# MCU103A_Connectors.net
KiCad netlist of a schematic drawn in Altium Designer
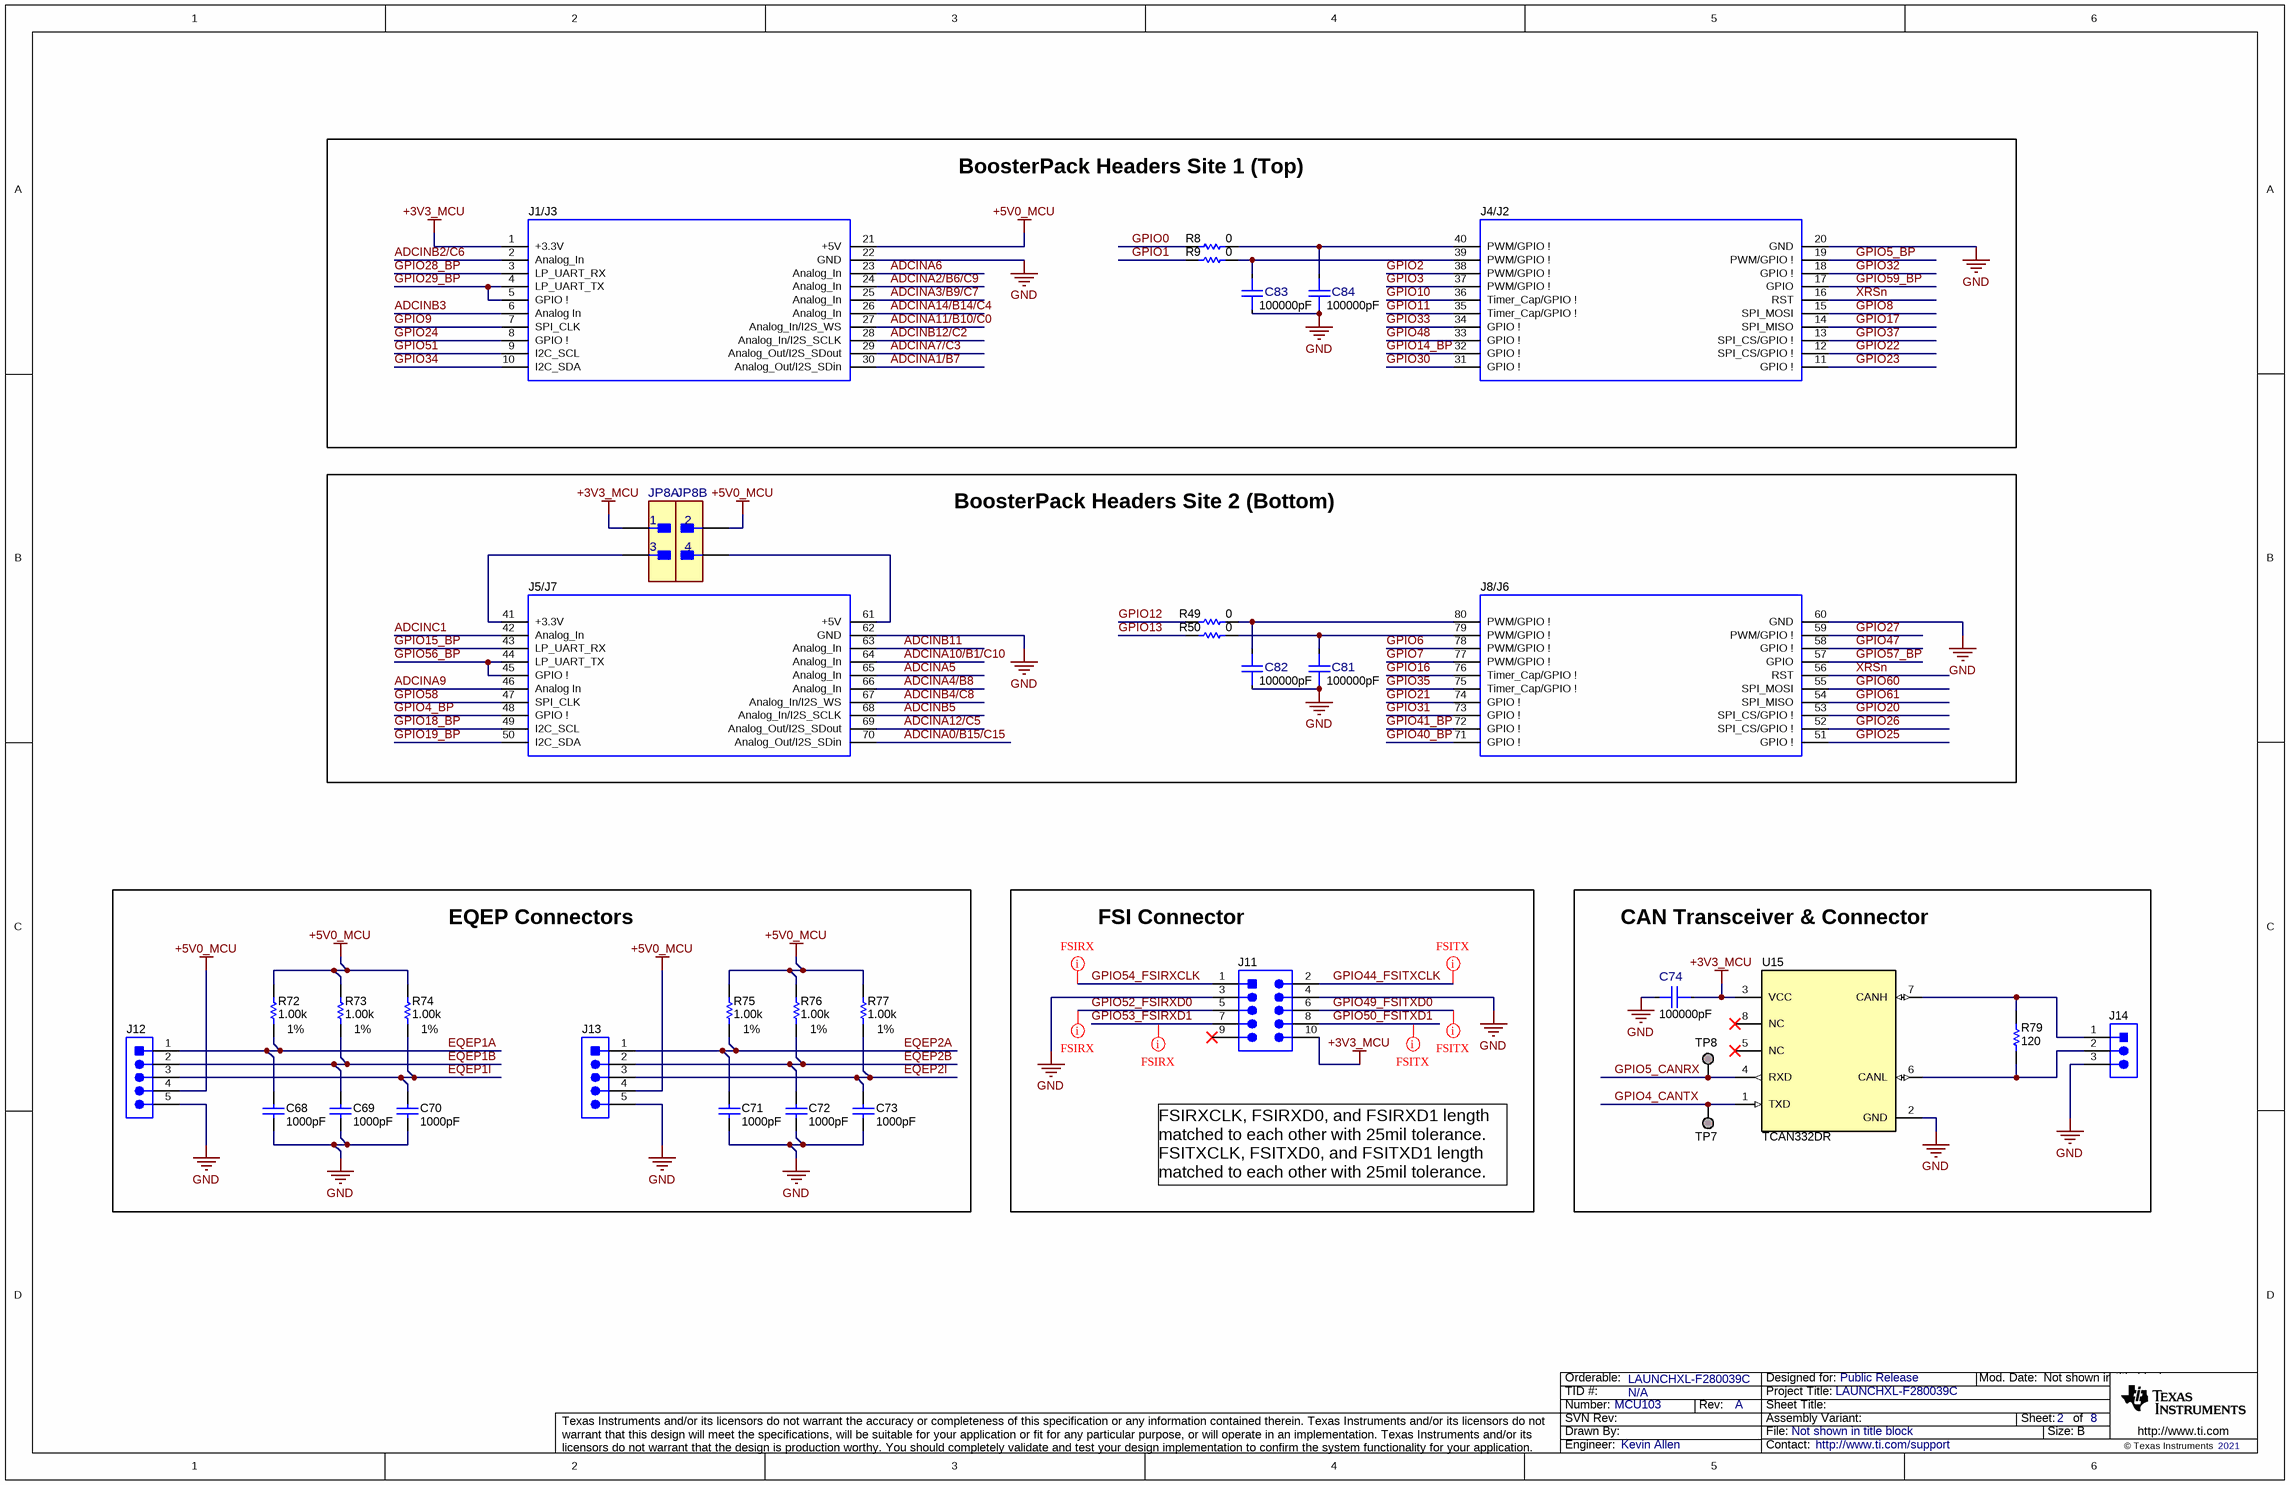
[diagram p0: MCU103A_Connectors.SchDoc]

(export (version "E")
  (design (tool "Eeschema 10.0.6"))
  (components
    (comp (ref "C68")
      (value "885012205061")
      (footprint "0402")
      (description "CAP, CERM, 1000 pF, 50 V, +/- 10%, X7R, 0402")
      (fields
        (field (name "VALUEDISPLAYED") "1000pF")
        (field (name "MANUFACTURER") "Wurth Elektronik")
        (field (name "PUBLISHER") "Texas Instruments")
      )
      (libsource (lib "Altium Vault - TI") (part "Capacitor"))
    )
    (comp (ref "C69")
      (value "885012205061")
      (footprint "0402")
      (description "CAP, CERM, 1000 pF, 50 V, +/- 10%, X7R, 0402")
      (fields
        (field (name "VALUEDISPLAYED") "1000pF")
        (field (name "MANUFACTURER") "Wurth Elektronik")
        (field (name "PUBLISHER") "Texas Instruments")
      )
      (libsource (lib "Altium Vault - TI") (part "Capacitor"))
    )
    (comp (ref "C70")
      (value "885012205061")
      (footprint "0402")
      (description "CAP, CERM, 1000 pF, 50 V, +/- 10%, X7R, 0402")
      (fields
        (field (name "VALUEDISPLAYED") "1000pF")
        (field (name "MANUFACTURER") "Wurth Elektronik")
        (field (name "PUBLISHER") "Texas Instruments")
      )
      (libsource (lib "Altium Vault - TI") (part "Capacitor"))
    )
    (comp (ref "C71")
      (value "885012205061")
      (footprint "0402")
      (description "CAP, CERM, 1000 pF, 50 V, +/- 10%, X7R, 0402")
      (fields
        (field (name "VALUEDISPLAYED") "1000pF")
        (field (name "MANUFACTURER") "Wurth Elektronik")
        (field (name "PUBLISHER") "Texas Instruments")
      )
      (libsource (lib "Altium Vault - TI") (part "Capacitor"))
    )
    (comp (ref "C72")
      (value "885012205061")
      (footprint "0402")
      (description "CAP, CERM, 1000 pF, 50 V, +/- 10%, X7R, 0402")
      (fields
        (field (name "VALUEDISPLAYED") "1000pF")
        (field (name "MANUFACTURER") "Wurth Elektronik")
        (field (name "PUBLISHER") "Texas Instruments")
      )
      (libsource (lib "Altium Vault - TI") (part "Capacitor"))
    )
    (comp (ref "C73")
      (value "885012205061")
      (footprint "0402")
      (description "CAP, CERM, 1000 pF, 50 V, +/- 10%, X7R, 0402")
      (fields
        (field (name "VALUEDISPLAYED") "1000pF")
        (field (name "MANUFACTURER") "Wurth Elektronik")
        (field (name "PUBLISHER") "Texas Instruments")
      )
      (libsource (lib "Altium Vault - TI") (part "Capacitor"))
    )
    (comp (ref "C74")
      (value "885012205018")
      (footprint "FP-885012205018_0402-MFG")
      (description "0.1µF ±10% 10V Ceramic Capacitor X7R 0402 (1005 Metric)")
      (fields
        (field (name "MANUFACTURER") "Wurth Electronics")
        (field (name "MOUSER PART NUMBER") "710-885012205018")
        (field (name "VALUEDISPLAYED") "100000pF")
      )
      (libsource (lib "Altium Vault - TI") (part "SYM-885012205018"))
    )
    (comp (ref "C81")
      (value "885012205018")
      (footprint "FP-885012205018_0402-MFG")
      (description "0.1µF ±10% 10V Ceramic Capacitor X7R 0402 (1005 Metric)")
      (fields
        (field (name "MANUFACTURER") "Wurth Electronics")
        (field (name "MOUSER PART NUMBER") "710-885012205018")
        (field (name "VALUEDISPLAYED") "100000pF")
      )
      (libsource (lib "Altium Vault - TI") (part "SYM-885012205018"))
    )
    (comp (ref "C82")
      (value "885012205018")
      (footprint "FP-885012205018_0402-MFG")
      (description "0.1µF ±10% 10V Ceramic Capacitor X7R 0402 (1005 Metric)")
      (fields
        (field (name "MANUFACTURER") "Wurth Electronics")
        (field (name "MOUSER PART NUMBER") "710-885012205018")
        (field (name "VALUEDISPLAYED") "100000pF")
      )
      (libsource (lib "Altium Vault - TI") (part "SYM-885012205018"))
    )
    (comp (ref "C83")
      (value "885012205018")
      (footprint "FP-885012205018_0402-MFG")
      (description "0.1µF ±10% 10V Ceramic Capacitor X7R 0402 (1005 Metric)")
      (fields
        (field (name "MANUFACTURER") "Wurth Electronics")
        (field (name "MOUSER PART NUMBER") "710-885012205018")
        (field (name "VALUEDISPLAYED") "100000pF")
      )
      (libsource (lib "Altium Vault - TI") (part "SYM-885012205018"))
    )
    (comp (ref "C84")
      (value "885012205018")
      (footprint "FP-885012205018_0402-MFG")
      (description "0.1µF ±10% 10V Ceramic Capacitor X7R 0402 (1005 Metric)")
      (fields
        (field (name "MANUFACTURER") "Wurth Electronics")
        (field (name "MOUSER PART NUMBER") "710-885012205018")
        (field (name "VALUEDISPLAYED") "100000pF")
      )
      (libsource (lib "Altium Vault - TI") (part "SYM-885012205018"))
    )
    (comp (ref "J1/J3")
      (value "SSQ-110-03-T-D")
      (footprint "BoosterPack_40pin_J1J3")
      (description "Receptacle, 2.54mm, 10x2, Tin, TH")
      (fields (field (name "ALTERNATE PARTNUMBER") "CRD-081413-A-G") (field (name "MANUFACTURER") "Samtec"))
      (libsource (lib "Altium Vault - TI") (part "BoosterPack_40pin_J1J3"))
    )
    (comp (ref "J4/J2")
      (value "SSQ-110-03-T-D")
      (footprint "BoosterPack_40pin_J2J4")
      (description "Receptacle, 2.54mm, 10x2, Tin, TH")
      (fields (field (name "ALTERNATE PARTNUMBER") "CRD-081413-A-G") (field (name "MANUFACTURER") "Samtec"))
      (libsource (lib "Altium Vault - TI") (part "BoosterPack_40pin_J2J4"))
    )
    (comp (ref "J5/J7")
      (value "SSQ-110-03-T-D")
      (footprint "BoosterPack_40pin_J5J7")
      (description "Receptacle, 2.54mm, 10x2, Tin, TH")
      (fields (field (name "ALTERNATE PARTNUMBER") "CRD-081413-A-G") (field (name "MANUFACTURER") "Samtec"))
      (libsource (lib "Altium Vault - TI") (part "BoosterPack_40pin_J5J7"))
    )
    (comp (ref "J8/J6")
      (value "SSQ-110-03-T-D")
      (footprint "BoosterPack_40pin_J6J8")
      (description "Receptacle, 2.54mm, 10x2, Tin, TH")
      (fields (field (name "ALTERNATE PARTNUMBER") "CRD-081413-A-G") (field (name "MANUFACTURER") "Samtec"))
      (libsource (lib "Altium Vault - TI") (part "BoosterPack_40pin_J6J8"))
    )
    (comp (ref "J11")
      (value "61301021121")
      (footprint "WURTH_61301021121")
      (description "Header, 2.54 mm, 5x2, Gold, TH")
      (fields (field (name "MANUFACTURER") "Wurth Elektronik"))
      (libsource (lib "Altium Vault - TI") (part "Header_5x2"))
    )
    (comp (ref "J12")
      (value "61300511121")
      (footprint "Wurth_61300511121")
      (description "Header, 2.54mm, 5x1, Gold, TH")
      (fields (field (name "MANUFACTURER") "Wurth Elektronik"))
      (libsource (lib "Altium Vault - TI") (part "Header_5x1"))
    )
    (comp (ref "J13")
      (value "61300511121")
      (footprint "Wurth_61300511121")
      (description "Header, 2.54mm, 5x1, Gold, TH")
      (fields (field (name "MANUFACTURER") "Wurth Elektronik"))
      (libsource (lib "Altium Vault - TI") (part "Header_5x1"))
    )
    (comp (ref "J14")
      (value "61300311121")
      (footprint "WURTH_61300311121")
      (description "Header, 2.54 mm, 3x1, Gold, TH")
      (fields (field (name "MANUFACTURER") "Wurth Elektronik") (field (name "PUBLISHER") "Texas Instruments"))
      (libsource (lib "Altium Vault - TI") (part "Header_3x1"))
    )
    (comp (ref "JP8")
      (value "61300421121")
      (footprint "FP-61300421121_HDR4-MFG")
      (description "THT Vertical Pin Header WR-PHD, Pitch 2.54 mm, Dual Row, 4 pins")
      (fields
        (field (name "MANUFACTURER") "Wurth Electronics")
        (field (name "MOUSER PART NUMBER") "710-61300421121")
      )
      (libsource (lib "") (part "SYM-61300421121_1"))
    )
    (comp (ref "R8")
      (value "RC0402JR-070RL")
      (footprint "0402")
      (description "RES, 0, 5%, 0.063 W, 0402")
      (fields
        (field (name "MANUFACTURER") "Yageo America")
        (field (name "VALUEDISPLAYED") "0")
        (field (name "PUBLISHER") "Texas Instruments")
      )
      (libsource (lib "Altium Vault - TI") (part "Resistor"))
    )
    (comp (ref "R9")
      (value "RC0402JR-070RL")
      (footprint "0402")
      (description "RES, 0, 5%, 0.063 W, 0402")
      (fields
        (field (name "MANUFACTURER") "Yageo America")
        (field (name "VALUEDISPLAYED") "0")
        (field (name "PUBLISHER") "Texas Instruments")
      )
      (libsource (lib "Altium Vault - TI") (part "Resistor"))
    )
    (comp (ref "R49")
      (value "RC0402JR-070RL")
      (footprint "0402")
      (description "RES, 0, 5%, 0.063 W, 0402")
      (fields
        (field (name "MANUFACTURER") "Yageo America")
        (field (name "VALUEDISPLAYED") "0")
        (field (name "PUBLISHER") "Texas Instruments")
      )
      (libsource (lib "Altium Vault - TI") (part "Resistor"))
    )
    (comp (ref "R50")
      (value "RC0402JR-070RL")
      (footprint "0402")
      (description "RES, 0, 5%, 0.063 W, 0402")
      (fields
        (field (name "MANUFACTURER") "Yageo America")
        (field (name "VALUEDISPLAYED") "0")
        (field (name "PUBLISHER") "Texas Instruments")
      )
      (libsource (lib "Altium Vault - TI") (part "Resistor"))
    )
    (comp (ref "R72")
      (value "CRCW04021K00FKED")
      (footprint "0402")
      (description "RES, 1.00 k, 1%, 0.063 W, AEC-Q200 Grade 0, 0402")
      (fields
        (field (name "VALUEDISPLAYED") "1.00k")
        (field (name "MANUFACTURER") "Vishay-Dale")
        (field (name "VALUE1") "1%")
      )
      (libsource (lib "Altium Vault - TI") (part "Resistor"))
    )
    (comp (ref "R73")
      (value "CRCW04021K00FKED")
      (footprint "0402")
      (description "RES, 1.00 k, 1%, 0.063 W, AEC-Q200 Grade 0, 0402")
      (fields
        (field (name "VALUEDISPLAYED") "1.00k")
        (field (name "MANUFACTURER") "Vishay-Dale")
        (field (name "VALUE1") "1%")
      )
      (libsource (lib "Altium Vault - TI") (part "Resistor"))
    )
    (comp (ref "R74")
      (value "CRCW04021K00FKED")
      (footprint "0402")
      (description "RES, 1.00 k, 1%, 0.063 W, AEC-Q200 Grade 0, 0402")
      (fields
        (field (name "VALUEDISPLAYED") "1.00k")
        (field (name "MANUFACTURER") "Vishay-Dale")
        (field (name "VALUE1") "1%")
      )
      (libsource (lib "Altium Vault - TI") (part "Resistor"))
    )
    (comp (ref "R75")
      (value "CRCW04021K00FKED")
      (footprint "0402")
      (description "RES, 1.00 k, 1%, 0.063 W, AEC-Q200 Grade 0, 0402")
      (fields
        (field (name "VALUEDISPLAYED") "1.00k")
        (field (name "MANUFACTURER") "Vishay-Dale")
        (field (name "VALUE1") "1%")
      )
      (libsource (lib "Altium Vault - TI") (part "Resistor"))
    )
    (comp (ref "R76")
      (value "CRCW04021K00FKED")
      (footprint "0402")
      (description "RES, 1.00 k, 1%, 0.063 W, AEC-Q200 Grade 0, 0402")
      (fields
        (field (name "VALUEDISPLAYED") "1.00k")
        (field (name "MANUFACTURER") "Vishay-Dale")
        (field (name "VALUE1") "1%")
      )
      (libsource (lib "Altium Vault - TI") (part "Resistor"))
    )
    (comp (ref "R77")
      (value "CRCW04021K00FKED")
      (footprint "0402")
      (description "RES, 1.00 k, 1%, 0.063 W, AEC-Q200 Grade 0, 0402")
      (fields
        (field (name "VALUEDISPLAYED") "1.00k")
        (field (name "MANUFACTURER") "Vishay-Dale")
        (field (name "VALUE1") "1%")
      )
      (libsource (lib "Altium Vault - TI") (part "Resistor"))
    )
    (comp (ref "R79")
      (value "RC0603FR-07120RL")
      (footprint "0603")
      (description "RES, 120, 1%, 0.1 W, 0603")
      (fields
        (field (name "VALUEDISPLAYED") "120")
        (field (name "MANUFACTURER") "Yageo America")
        (field (name "PUBLISHER") "Texas Instruments")
      )
      (libsource (lib "Altium Vault - TI") (part "Resistor"))
    )
    (comp (ref "TP7")
      (value "TESTPOINT")
      (footprint "TP_50MIL-25MILHOLE")
      (description "TEST POINT.  No entry in BOM.")
      (libsource (lib "Altium Vault - TI") (part "TESTPOINT"))
    )
    (comp (ref "TP8")
      (value "TESTPOINT")
      (footprint "TP_50MIL-25MILHOLE")
      (description "TEST POINT.  No entry in BOM.")
      (libsource (lib "Altium Vault - TI") (part "TESTPOINT"))
    )
    (comp (ref "U15")
      (value "TCAN332DR")
      (footprint "D0008A_N")
      (description "3.3-V CAN Transceivers, D0008A (SOIC-8)")
      (fields
        (field (name "ALTERNATE PARTNUMBER") "TCAN332D")
        (field (name "MANUFACTURER") "Texas Instruments")
        (field (name "PARTNUMBER") "TCAN332DR")
      )
      (libsource (lib "Altium Vault - TI") (part "TCAN332"))
    )
  )
  (nets
    (net (code "1") (name "+3V3_MCU") (class "Default")
      (node (ref "C74") (pin "1") (pinfunction "1_1") (pintype "passive"))
      (node (ref "J1/J3") (pin "1") (pinfunction "+3.3V_1") (pintype "power_in"))
      (node (ref "J11") (pin "10") (pinfunction "10_10") (pintype "passive"))
      (node (ref "JP8") (pin "1") (pinfunction "1_1") (pintype "passive"))
      (node (ref "U15") (pin "3") (pinfunction "VCC_3") (pintype "power_in"))
    )
    (net (code "2") (name "+5V0_MCU") (class "Default")
      (node (ref "J1/J3") (pin "21") (pinfunction "+5V_21") (pintype "power_in"))
      (node (ref "J12") (pin "4") (pinfunction "4_4") (pintype "passive"))
      (node (ref "J13") (pin "4") (pinfunction "4_4") (pintype "passive"))
      (node (ref "JP8") (pin "2") (pinfunction "2_2") (pintype "passive"))
      (node (ref "R72") (pin "2") (pinfunction "2_2") (pintype "passive"))
      (node (ref "R73") (pin "2") (pinfunction "2_2") (pintype "passive"))
      (node (ref "R74") (pin "2") (pinfunction "2_2") (pintype "passive"))
      (node (ref "R75") (pin "2") (pinfunction "2_2") (pintype "passive"))
      (node (ref "R76") (pin "2") (pinfunction "2_2") (pintype "passive"))
      (node (ref "R77") (pin "2") (pinfunction "2_2") (pintype "passive"))
    )
    (net (code "3") (name "/ADCINA0{slash}B15{slash}C15") (class "Default")
      (node (ref "J5/J7") (pin "70") (pinfunction "Analog_Out/I2S_SDin_70") (pintype "passive"))
    )
    (net (code "4") (name "/ADCINA1{slash}B7") (class "Default")
      (node (ref "J1/J3") (pin "30") (pinfunction "Analog_Out/I2S_SDin_30") (pintype "passive"))
    )
    (net (code "5") (name "/ADCINA2{slash}B6{slash}C9") (class "Default")
      (node (ref "J1/J3") (pin "24") (pinfunction "Analog_In_24") (pintype "passive"))
    )
    (net (code "6") (name "/ADCINA3{slash}B9{slash}C7") (class "Default")
      (node (ref "J1/J3") (pin "25") (pinfunction "Analog_In_25") (pintype "passive"))
    )
    (net (code "7") (name "/ADCINA4{slash}B8") (class "Default")
      (node (ref "J5/J7") (pin "66") (pinfunction "Analog_In_66") (pintype "passive"))
    )
    (net (code "8") (name "/ADCINA5") (class "Default")
      (node (ref "J5/J7") (pin "65") (pinfunction "Analog_In_65") (pintype "passive"))
    )
    (net (code "9") (name "/ADCINA6") (class "Default")
      (node (ref "J1/J3") (pin "23") (pinfunction "Analog_In_23") (pintype "passive"))
    )
    (net (code "10") (name "/ADCINA7{slash}C3") (class "Default")
      (node (ref "J1/J3") (pin "29") (pinfunction "Analog_Out/I2S_SDout_29") (pintype "passive"))
    )
    (net (code "11") (name "/ADCINA9") (class "Default")
      (node (ref "J5/J7") (pin "46") (pinfunction "Analog_In_46") (pintype "passive"))
    )
    (net (code "12") (name "/ADCINA10{slash}B1{slash}C10") (class "Default")
      (node (ref "J5/J7") (pin "64") (pinfunction "Analog_In_64") (pintype "passive"))
    )
    (net (code "13") (name "/ADCINA11{slash}B10{slash}C0") (class "Default")
      (node (ref "J1/J3") (pin "27") (pinfunction "Analog_In/I2S_WS_27") (pintype "passive"))
    )
    (net (code "14") (name "/ADCINA12{slash}C5") (class "Default")
      (node (ref "J5/J7") (pin "69") (pinfunction "Analog_Out/I2S_SDout_69") (pintype "passive"))
    )
    (net (code "15") (name "/ADCINA14{slash}B14{slash}C4") (class "Default")
      (node (ref "J1/J3") (pin "26") (pinfunction "Analog_In_26") (pintype "passive"))
    )
    (net (code "16") (name "/ADCINB2{slash}C6") (class "Default")
      (node (ref "J1/J3") (pin "2") (pinfunction "Analog_In_2") (pintype "passive"))
    )
    (net (code "17") (name "/ADCINB3") (class "Default")
      (node (ref "J1/J3") (pin "6") (pinfunction "Analog_In_6") (pintype "passive"))
    )
    (net (code "18") (name "/ADCINB4{slash}C8") (class "Default")
      (node (ref "J5/J7") (pin "67") (pinfunction "Analog_In/I2S_WS_67") (pintype "passive"))
    )
    (net (code "19") (name "/ADCINB5") (class "Default")
      (node (ref "J5/J7") (pin "68") (pinfunction "Analog_In/I2S_SCLK_68") (pintype "passive"))
    )
    (net (code "20") (name "/ADCINB11") (class "Default")
      (node (ref "J5/J7") (pin "63") (pinfunction "Analog_In_63") (pintype "passive"))
    )
    (net (code "21") (name "/ADCINB12{slash}C2") (class "Default")
      (node (ref "J1/J3") (pin "28") (pinfunction "Analog_In/I2S_SCLK_28") (pintype "passive"))
    )
    (net (code "22") (name "/ADCINC1") (class "Default")
      (node (ref "J5/J7") (pin "42") (pinfunction "Analog_In_42") (pintype "passive"))
    )
    (net (code "23") (name "/EQEP1A") (class "Default")
      (node (ref "C68") (pin "1") (pinfunction "1_1") (pintype "passive"))
      (node (ref "J12") (pin "1") (pinfunction "1_1") (pintype "passive"))
      (node (ref "R72") (pin "1") (pinfunction "1_1") (pintype "passive"))
    )
    (net (code "24") (name "/EQEP1B") (class "Default")
      (node (ref "C69") (pin "1") (pinfunction "1_1") (pintype "passive"))
      (node (ref "J12") (pin "2") (pinfunction "2_2") (pintype "passive"))
      (node (ref "R73") (pin "1") (pinfunction "1_1") (pintype "passive"))
    )
    (net (code "25") (name "/EQEP1I") (class "Default")
      (node (ref "C70") (pin "1") (pinfunction "1_1") (pintype "passive"))
      (node (ref "J12") (pin "3") (pinfunction "3_3") (pintype "passive"))
      (node (ref "R74") (pin "1") (pinfunction "1_1") (pintype "passive"))
    )
    (net (code "26") (name "/EQEP2A") (class "Default")
      (node (ref "C71") (pin "1") (pinfunction "1_1") (pintype "passive"))
      (node (ref "J13") (pin "1") (pinfunction "1_1") (pintype "passive"))
      (node (ref "R75") (pin "1") (pinfunction "1_1") (pintype "passive"))
    )
    (net (code "27") (name "/EQEP2B") (class "Default")
      (node (ref "C72") (pin "1") (pinfunction "1_1") (pintype "passive"))
      (node (ref "J13") (pin "2") (pinfunction "2_2") (pintype "passive"))
      (node (ref "R76") (pin "1") (pinfunction "1_1") (pintype "passive"))
    )
    (net (code "28") (name "/EQEP2I") (class "Default")
      (node (ref "C73") (pin "1") (pinfunction "1_1") (pintype "passive"))
      (node (ref "J13") (pin "3") (pinfunction "3_3") (pintype "passive"))
      (node (ref "R77") (pin "1") (pinfunction "1_1") (pintype "passive"))
    )
    (net (code "29") (name "/GPIO0") (class "Default")
      (node (ref "R8") (pin "1") (pinfunction "1_1") (pintype "passive"))
    )
    (net (code "30") (name "/GPIO1") (class "Default")
      (node (ref "R9") (pin "1") (pinfunction "1_1") (pintype "passive"))
    )
    (net (code "31") (name "/GPIO2") (class "Default")
      (node (ref "J4/J2") (pin "38") (pinfunction "PWM/GPIO_!_38") (pintype "passive"))
    )
    (net (code "32") (name "/GPIO3") (class "Default")
      (node (ref "J4/J2") (pin "37") (pinfunction "PWM/GPIO_!_37") (pintype "passive"))
    )
    (net (code "33") (name "/GPIO4_BP") (class "Default")
      (node (ref "J5/J7") (pin "48") (pinfunction "GPIO_!_48") (pintype "passive"))
    )
    (net (code "34") (name "/GPIO4_CANTX") (class "Default")
      (node (ref "TP7") (pin "1") (pintype "passive"))
      (node (ref "U15") (pin "1") (pinfunction "TXD_1") (pintype "input"))
    )
    (net (code "35") (name "/GPIO5_BP") (class "Default")
      (node (ref "J4/J2") (pin "19") (pinfunction "PWM/GPIO_!_19") (pintype "passive"))
    )
    (net (code "36") (name "/GPIO5_CANRX") (class "Default")
      (node (ref "TP8") (pin "1") (pintype "passive"))
      (node (ref "U15") (pin "4") (pinfunction "RXD_4") (pintype "output"))
    )
    (net (code "37") (name "/GPIO6") (class "Default")
      (node (ref "J8/J6") (pin "78") (pinfunction "PWM/GPIO_!_78") (pintype "passive"))
    )
    (net (code "38") (name "/GPIO7") (class "Default")
      (node (ref "J8/J6") (pin "77") (pinfunction "PWM/GPIO_!_77") (pintype "passive"))
    )
    (net (code "39") (name "/GPIO8") (class "Default")
      (node (ref "J4/J2") (pin "15") (pinfunction "SPI_MOSI_15") (pintype "passive"))
    )
    (net (code "40") (name "/GPIO9") (class "Default")
      (node (ref "J1/J3") (pin "7") (pinfunction "SPI_CLK_7") (pintype "passive"))
    )
    (net (code "41") (name "/GPIO10") (class "Default")
      (node (ref "J4/J2") (pin "36") (pinfunction "Timer_Cap/GPIO_!_36") (pintype "passive"))
    )
    (net (code "42") (name "/GPIO11") (class "Default")
      (node (ref "J4/J2") (pin "35") (pinfunction "Timer_Cap/GPIO_!_35") (pintype "passive"))
    )
    (net (code "43") (name "/GPIO12") (class "Default")
      (node (ref "R49") (pin "1") (pinfunction "1_1") (pintype "passive"))
    )
    (net (code "44") (name "/GPIO13") (class "Default")
      (node (ref "R50") (pin "1") (pinfunction "1_1") (pintype "passive"))
    )
    (net (code "45") (name "/GPIO14_BP") (class "Default")
      (node (ref "J4/J2") (pin "32") (pinfunction "GPIO_!_32") (pintype "passive"))
    )
    (net (code "46") (name "/GPIO15_BP") (class "Default")
      (node (ref "J5/J7") (pin "43") (pinfunction "LP_UART_RX_43") (pintype "passive"))
    )
    (net (code "47") (name "/GPIO16") (class "Default")
      (node (ref "J8/J6") (pin "76") (pinfunction "Timer_Cap/GPIO_!_76") (pintype "passive"))
    )
    (net (code "48") (name "/GPIO17") (class "Default")
      (node (ref "J4/J2") (pin "14") (pinfunction "SPI_MISO_14") (pintype "passive"))
    )
    (net (code "49") (name "/GPIO18_BP") (class "Default")
      (node (ref "J5/J7") (pin "49") (pinfunction "I2C_SCL_49") (pintype "passive"))
    )
    (net (code "50") (name "/GPIO19_BP") (class "Default")
      (node (ref "J5/J7") (pin "50") (pinfunction "I2C_SDA_50") (pintype "passive"))
    )
    (net (code "51") (name "/GPIO20") (class "Default")
      (node (ref "J8/J6") (pin "53") (pinfunction "SPI_CS/GPIO_!_53") (pintype "passive"))
    )
    (net (code "52") (name "/GPIO21") (class "Default")
      (node (ref "J8/J6") (pin "74") (pinfunction "GPIO_!_74") (pintype "passive"))
    )
    (net (code "53") (name "/GPIO22") (class "Default")
      (node (ref "J4/J2") (pin "12") (pinfunction "SPI_CS/GPIO_!_12") (pintype "passive"))
    )
    (net (code "54") (name "/GPIO23") (class "Default")
      (node (ref "J4/J2") (pin "11") (pinfunction "GPIO_!_11") (pintype "passive"))
    )
    (net (code "55") (name "/GPIO24") (class "Default")
      (node (ref "J1/J3") (pin "8") (pinfunction "GPIO_!_8") (pintype "passive"))
    )
    (net (code "56") (name "/GPIO25") (class "Default")
      (node (ref "J8/J6") (pin "51") (pinfunction "GPIO_!_51") (pintype "passive"))
    )
    (net (code "57") (name "/GPIO26") (class "Default")
      (node (ref "J8/J6") (pin "52") (pinfunction "SPI_CS/GPIO_!_52") (pintype "passive"))
    )
    (net (code "58") (name "/GPIO27") (class "Default")
      (node (ref "J8/J6") (pin "59") (pinfunction "PWM/GPIO_!_59") (pintype "passive"))
    )
    (net (code "59") (name "/GPIO28_BP") (class "Default")
      (node (ref "J1/J3") (pin "3") (pinfunction "LP_UART_RX_3") (pintype "passive"))
    )
    (net (code "60") (name "/GPIO29_BP") (class "Default")
      (node (ref "J1/J3") (pin "4") (pinfunction "LP_UART_TX_4") (pintype "passive"))
      (node (ref "J1/J3") (pin "5") (pinfunction "GPIO_!_5") (pintype "passive"))
    )
    (net (code "61") (name "/GPIO30") (class "Default")
      (node (ref "J4/J2") (pin "31") (pinfunction "GPIO_!_31") (pintype "passive"))
    )
    (net (code "62") (name "/GPIO31") (class "Default")
      (node (ref "J8/J6") (pin "73") (pinfunction "GPIO_!_73") (pintype "passive"))
    )
    (net (code "63") (name "/GPIO32") (class "Default")
      (node (ref "J4/J2") (pin "18") (pinfunction "GPIO_!_18") (pintype "passive"))
    )
    (net (code "64") (name "/GPIO33") (class "Default")
      (node (ref "J4/J2") (pin "34") (pinfunction "GPIO_!_34") (pintype "passive"))
    )
    (net (code "65") (name "/GPIO34") (class "Default")
      (node (ref "J1/J3") (pin "10") (pinfunction "I2C_SDA_10") (pintype "passive"))
    )
    (net (code "66") (name "/GPIO35") (class "Default")
      (node (ref "J8/J6") (pin "75") (pinfunction "Timer_Cap/GPIO_!_75") (pintype "passive"))
    )
    (net (code "67") (name "/GPIO37") (class "Default")
      (node (ref "J4/J2") (pin "13") (pinfunction "SPI_CS/GPIO_!_13") (pintype "passive"))
    )
    (net (code "68") (name "/GPIO40_BP") (class "Default")
      (node (ref "J8/J6") (pin "71") (pinfunction "GPIO_!_71") (pintype "passive"))
    )
    (net (code "69") (name "/GPIO41_BP") (class "Default")
      (node (ref "J8/J6") (pin "72") (pinfunction "GPIO_!_72") (pintype "passive"))
    )
    (net (code "70") (name "/GPIO44_FSITXCLK") (class "Default")
      (node (ref "J11") (pin "2") (pinfunction "2_2") (pintype "passive"))
    )
    (net (code "71") (name "/GPIO47") (class "Default")
      (node (ref "J8/J6") (pin "58") (pinfunction "GPIO_!_58") (pintype "passive"))
    )
    (net (code "72") (name "/GPIO48") (class "Default")
      (node (ref "J4/J2") (pin "33") (pinfunction "GPIO_!_33") (pintype "passive"))
    )
    (net (code "73") (name "/GPIO49_FSITXD0") (class "Default")
      (node (ref "J11") (pin "6") (pinfunction "6_6") (pintype "passive"))
    )
    (net (code "74") (name "/GPIO50_FSITXD1") (class "Default")
      (node (ref "J11") (pin "8") (pinfunction "8_8") (pintype "passive"))
    )
    (net (code "75") (name "/GPIO51") (class "Default")
      (node (ref "J1/J3") (pin "9") (pinfunction "I2C_SCL_9") (pintype "passive"))
    )
    (net (code "76") (name "/GPIO52_FSIRXD0") (class "Default")
      (node (ref "J11") (pin "5") (pinfunction "5_5") (pintype "passive"))
    )
    (net (code "77") (name "/GPIO53_FSIRXD1") (class "Default")
      (node (ref "J11") (pin "7") (pinfunction "7_7") (pintype "passive"))
    )
    (net (code "78") (name "/GPIO54_FSIRXCLK") (class "Default")
      (node (ref "J11") (pin "1") (pinfunction "1_1") (pintype "passive"))
    )
    (net (code "79") (name "/GPIO56_BP") (class "Default")
      (node (ref "J5/J7") (pin "44") (pinfunction "LP_UART_TX_44") (pintype "passive"))
      (node (ref "J5/J7") (pin "45") (pinfunction "GPIO_!_45") (pintype "passive"))
    )
    (net (code "80") (name "/GPIO57_BP") (class "Default")
      (node (ref "J8/J6") (pin "57") (pinfunction "GPIO_57") (pintype "passive"))
    )
    (net (code "81") (name "/GPIO58") (class "Default")
      (node (ref "J5/J7") (pin "47") (pinfunction "SPI_CLK_47") (pintype "passive"))
    )
    (net (code "82") (name "/GPIO59_BP") (class "Default")
      (node (ref "J4/J2") (pin "17") (pinfunction "GPIO_17") (pintype "passive"))
    )
    (net (code "83") (name "/GPIO60") (class "Default")
      (node (ref "J8/J6") (pin "55") (pinfunction "SPI_MOSI_55") (pintype "passive"))
    )
    (net (code "84") (name "/GPIO61") (class "Default")
      (node (ref "J8/J6") (pin "54") (pinfunction "SPI_MISO_54") (pintype "passive"))
    )
    (net (code "85") (name "/XRSn") (class "Default")
      (node (ref "J4/J2") (pin "16") (pinfunction "RST_16") (pintype "passive"))
      (node (ref "J8/J6") (pin "56") (pinfunction "RST_56") (pintype "passive"))
    )
    (net (code "86") (name "GND") (class "Default")
      (node (ref "C68") (pin "2") (pinfunction "2_2") (pintype "passive"))
      (node (ref "C69") (pin "2") (pinfunction "2_2") (pintype "passive"))
      (node (ref "C70") (pin "2") (pinfunction "2_2") (pintype "passive"))
      (node (ref "C71") (pin "2") (pinfunction "2_2") (pintype "passive"))
      (node (ref "C72") (pin "2") (pinfunction "2_2") (pintype "passive"))
      (node (ref "C73") (pin "2") (pinfunction "2_2") (pintype "passive"))
      (node (ref "C74") (pin "2") (pinfunction "2_2") (pintype "passive"))
      (node (ref "C81") (pin "1") (pinfunction "1_1") (pintype "passive"))
      (node (ref "C82") (pin "1") (pinfunction "1_1") (pintype "passive"))
      (node (ref "C83") (pin "1") (pinfunction "1_1") (pintype "passive"))
      (node (ref "C84") (pin "1") (pinfunction "1_1") (pintype "passive"))
      (node (ref "J1/J3") (pin "22") (pinfunction "GND_22") (pintype "power_in"))
      (node (ref "J11") (pin "3") (pinfunction "3_3") (pintype "passive"))
      (node (ref "J11") (pin "4") (pinfunction "4_4") (pintype "passive"))
      (node (ref "J12") (pin "5") (pinfunction "5_5") (pintype "passive"))
      (node (ref "J13") (pin "5") (pinfunction "5_5") (pintype "passive"))
      (node (ref "J14") (pin "3") (pinfunction "3_3") (pintype "passive"))
      (node (ref "J4/J2") (pin "20") (pinfunction "GND_20") (pintype "power_in"))
      (node (ref "J5/J7") (pin "62") (pinfunction "GND_62") (pintype "power_in"))
      (node (ref "J8/J6") (pin "60") (pinfunction "GND_60") (pintype "power_in"))
      (node (ref "U15") (pin "2") (pinfunction "GND_2") (pintype "power_in"))
    )
    (net (code "87") (name "Net-(C81-Pad2)") (class "Default")
      (node (ref "C81") (pin "2") (pinfunction "2_2") (pintype "passive"))
      (node (ref "J8/J6") (pin "79") (pinfunction "PWM/GPIO_!_79") (pintype "passive"))
      (node (ref "R50") (pin "2") (pinfunction "2_2") (pintype "passive"))
    )
    (net (code "88") (name "Net-(C82-Pad2)") (class "Default")
      (node (ref "C82") (pin "2") (pinfunction "2_2") (pintype "passive"))
      (node (ref "J8/J6") (pin "80") (pinfunction "PWM/GPIO_!_80") (pintype "passive"))
      (node (ref "R49") (pin "2") (pinfunction "2_2") (pintype "passive"))
    )
    (net (code "89") (name "Net-(C83-Pad2)") (class "Default")
      (node (ref "C83") (pin "2") (pinfunction "2_2") (pintype "passive"))
      (node (ref "J4/J2") (pin "39") (pinfunction "PWM/GPIO_!_39") (pintype "passive"))
      (node (ref "R9") (pin "2") (pinfunction "2_2") (pintype "passive"))
    )
    (net (code "90") (name "Net-(C84-Pad2)") (class "Default")
      (node (ref "C84") (pin "2") (pinfunction "2_2") (pintype "passive"))
      (node (ref "J4/J2") (pin "40") (pinfunction "PWM/GPIO_!_40") (pintype "passive"))
      (node (ref "R8") (pin "2") (pinfunction "2_2") (pintype "passive"))
    )
    (net (code "91") (name "Net-(J5/J7-+3.3V)") (class "Default")
      (node (ref "J5/J7") (pin "41") (pinfunction "+3.3V_41") (pintype "power_in"))
      (node (ref "JP8") (pin "3") (pinfunction "3_3") (pintype "passive"))
    )
    (net (code "92") (name "Net-(J5/J7-+5V)") (class "Default")
      (node (ref "J5/J7") (pin "61") (pinfunction "+5V_61") (pintype "power_in"))
      (node (ref "JP8") (pin "4") (pinfunction "4_4") (pintype "passive"))
    )
    (net (code "93") (name "Net-(U15-CANH)") (class "Default")
      (node (ref "J14") (pin "1") (pinfunction "1_1") (pintype "passive"))
      (node (ref "R79") (pin "2") (pinfunction "2_2") (pintype "passive"))
      (node (ref "U15") (pin "7") (pinfunction "CANH_7") (pintype "bidirectional"))
    )
    (net (code "94") (name "Net-(U15-CANL)") (class "Default")
      (node (ref "J14") (pin "2") (pinfunction "2_2") (pintype "passive"))
      (node (ref "R79") (pin "1") (pinfunction "1_1") (pintype "passive"))
      (node (ref "U15") (pin "6") (pinfunction "CANL_6") (pintype "bidirectional"))
    )
    (net (code "95") (name "unconnected-(J11-Pad9)") (class "Default")
      (node (ref "J11") (pin "9") (pinfunction "9_9") (pintype "passive+no_connect"))
    )
    (net (code "96") (name "unconnected-(U15-NC-Pad5)") (class "Default")
      (node (ref "U15") (pin "5") (pinfunction "NC_5") (pintype "passive+no_connect"))
    )
    (net (code "97") (name "unconnected-(U15-NC-Pad8)") (class "Default")
      (node (ref "U15") (pin "8") (pinfunction "NC_8") (pintype "passive+no_connect"))
    )
  )
)
